# passenger.net
KiCad netlist of a schematic drawn in Altium Designer
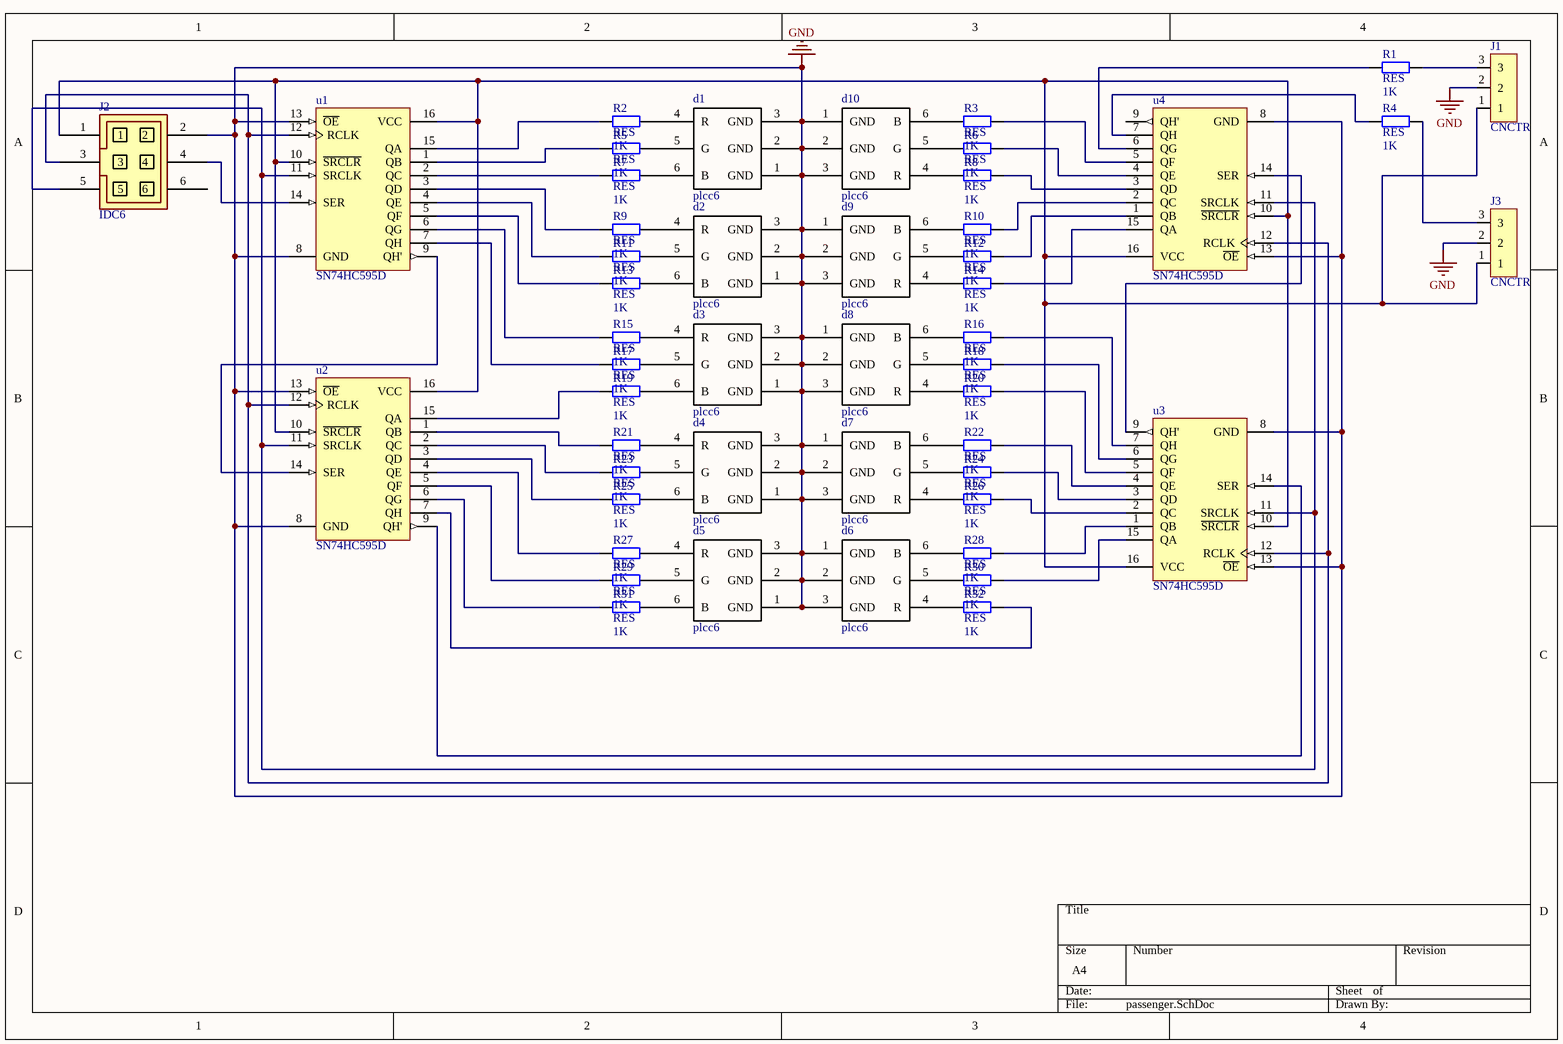
[diagram p0: passenger.SchDoc]

(export (version "E")
  (design (tool "Eeschema 10.0.6"))
  (components
    (comp (ref "d1") (value "plcc6") (footprint "plcc6") (libsource (lib "std") (part "plcc6")))
    (comp (ref "d2") (value "plcc6") (footprint "plcc6") (libsource (lib "std") (part "plcc6")))
    (comp (ref "d3") (value "plcc6") (footprint "plcc6") (libsource (lib "std") (part "plcc6")))
    (comp (ref "d4") (value "plcc6") (footprint "plcc6") (libsource (lib "std") (part "plcc6")))
    (comp (ref "d5") (value "plcc6") (footprint "plcc6") (libsource (lib "std") (part "plcc6")))
    (comp (ref "d6") (value "plcc6") (footprint "plcc6") (libsource (lib "std") (part "plcc6")))
    (comp (ref "d7") (value "plcc6") (footprint "plcc6") (libsource (lib "std") (part "plcc6")))
    (comp (ref "d8") (value "plcc6") (footprint "plcc6") (libsource (lib "std") (part "plcc6")))
    (comp (ref "d9") (value "plcc6") (footprint "plcc6") (libsource (lib "std") (part "plcc6")))
    (comp (ref "d10") (value "plcc6") (footprint "plcc6") (libsource (lib "std") (part "plcc6")))
    (comp (ref "J1")
      (value "CNCTR")
      (footprint "CNCTR_1X3")
      (description "3pin connector")
      (libsource (lib "std") (part "Connector"))
    )
    (comp (ref "J2")
      (value "IDC6")
      (footprint "IDC6")
      (description "6pin IDC connector")
      (libsource (lib "std") (part "IDC6"))
    )
    (comp (ref "J3")
      (value "CNCTR")
      (footprint "CNCTR_1X3")
      (description "3pin connector")
      (libsource (lib "std") (part "Connector"))
    )
    (comp (ref "R1")
      (value "RES")
      (footprint "RESC1608X06M")
      (description "Resistor")
      (fields (field (name "ALTIUM_VALUE") "1K") (field (name "PUBLISHER") "Altium Limited"))
      (libsource (lib "std") (part "RES"))
    )
    (comp (ref "R2")
      (value "RES")
      (footprint "RESC1608X06M")
      (description "Resistor")
      (fields (field (name "ALTIUM_VALUE") "1K") (field (name "PUBLISHER") "Altium Limited"))
      (libsource (lib "std") (part "RES"))
    )
    (comp (ref "R3")
      (value "RES")
      (footprint "RESC1608X06M")
      (description "Resistor")
      (fields (field (name "ALTIUM_VALUE") "1K") (field (name "PUBLISHER") "Altium Limited"))
      (libsource (lib "std") (part "RES"))
    )
    (comp (ref "R4")
      (value "RES")
      (footprint "RESC1608X06M")
      (description "Resistor")
      (fields (field (name "ALTIUM_VALUE") "1K") (field (name "PUBLISHER") "Altium Limited"))
      (libsource (lib "std") (part "RES"))
    )
    (comp (ref "R5")
      (value "RES")
      (footprint "RESC1608X06M")
      (description "Resistor")
      (fields (field (name "ALTIUM_VALUE") "1K") (field (name "PUBLISHER") "Altium Limited"))
      (libsource (lib "std") (part "RES"))
    )
    (comp (ref "R6")
      (value "RES")
      (footprint "RESC1608X06M")
      (description "Resistor")
      (fields (field (name "ALTIUM_VALUE") "1K") (field (name "PUBLISHER") "Altium Limited"))
      (libsource (lib "std") (part "RES"))
    )
    (comp (ref "R7")
      (value "RES")
      (footprint "RESC1608X06M")
      (description "Resistor")
      (fields (field (name "ALTIUM_VALUE") "1K") (field (name "PUBLISHER") "Altium Limited"))
      (libsource (lib "std") (part "RES"))
    )
    (comp (ref "R8")
      (value "RES")
      (footprint "RESC1608X06M")
      (description "Resistor")
      (fields (field (name "ALTIUM_VALUE") "1K") (field (name "PUBLISHER") "Altium Limited"))
      (libsource (lib "std") (part "RES"))
    )
    (comp (ref "R9")
      (value "RES")
      (footprint "RESC1608X06M")
      (description "Resistor")
      (fields (field (name "ALTIUM_VALUE") "1K") (field (name "PUBLISHER") "Altium Limited"))
      (libsource (lib "std") (part "RES"))
    )
    (comp (ref "R10")
      (value "RES")
      (footprint "RESC1608X06M")
      (description "Resistor")
      (fields (field (name "ALTIUM_VALUE") "1K") (field (name "PUBLISHER") "Altium Limited"))
      (libsource (lib "std") (part "RES"))
    )
    (comp (ref "R11")
      (value "RES")
      (footprint "RESC1608X06M")
      (description "Resistor")
      (fields (field (name "ALTIUM_VALUE") "1K") (field (name "PUBLISHER") "Altium Limited"))
      (libsource (lib "std") (part "RES"))
    )
    (comp (ref "R12")
      (value "RES")
      (footprint "RESC1608X06M")
      (description "Resistor")
      (fields (field (name "ALTIUM_VALUE") "1K") (field (name "PUBLISHER") "Altium Limited"))
      (libsource (lib "std") (part "RES"))
    )
    (comp (ref "R13")
      (value "RES")
      (footprint "RESC1608X06M")
      (description "Resistor")
      (fields (field (name "ALTIUM_VALUE") "1K") (field (name "PUBLISHER") "Altium Limited"))
      (libsource (lib "std") (part "RES"))
    )
    (comp (ref "R14")
      (value "RES")
      (footprint "RESC1608X06M")
      (description "Resistor")
      (fields (field (name "ALTIUM_VALUE") "1K") (field (name "PUBLISHER") "Altium Limited"))
      (libsource (lib "std") (part "RES"))
    )
    (comp (ref "R15")
      (value "RES")
      (footprint "RESC1608X06M")
      (description "Resistor")
      (fields (field (name "ALTIUM_VALUE") "1K") (field (name "PUBLISHER") "Altium Limited"))
      (libsource (lib "std") (part "RES"))
    )
    (comp (ref "R16")
      (value "RES")
      (footprint "RESC1608X06M")
      (description "Resistor")
      (fields (field (name "ALTIUM_VALUE") "1K") (field (name "PUBLISHER") "Altium Limited"))
      (libsource (lib "std") (part "RES"))
    )
    (comp (ref "R17")
      (value "RES")
      (footprint "RESC1608X06M")
      (description "Resistor")
      (fields (field (name "ALTIUM_VALUE") "1K") (field (name "PUBLISHER") "Altium Limited"))
      (libsource (lib "std") (part "RES"))
    )
    (comp (ref "R18")
      (value "RES")
      (footprint "RESC1608X06M")
      (description "Resistor")
      (fields (field (name "ALTIUM_VALUE") "1K") (field (name "PUBLISHER") "Altium Limited"))
      (libsource (lib "std") (part "RES"))
    )
    (comp (ref "R19")
      (value "RES")
      (footprint "RESC1608X06M")
      (description "Resistor")
      (fields (field (name "ALTIUM_VALUE") "1K") (field (name "PUBLISHER") "Altium Limited"))
      (libsource (lib "std") (part "RES"))
    )
    (comp (ref "R20")
      (value "RES")
      (footprint "RESC1608X06M")
      (description "Resistor")
      (fields (field (name "ALTIUM_VALUE") "1K") (field (name "PUBLISHER") "Altium Limited"))
      (libsource (lib "std") (part "RES"))
    )
    (comp (ref "R21")
      (value "RES")
      (footprint "RESC1608X06M")
      (description "Resistor")
      (fields (field (name "ALTIUM_VALUE") "1K") (field (name "PUBLISHER") "Altium Limited"))
      (libsource (lib "std") (part "RES"))
    )
    (comp (ref "R22")
      (value "RES")
      (footprint "RESC1608X06M")
      (description "Resistor")
      (fields (field (name "ALTIUM_VALUE") "1K") (field (name "PUBLISHER") "Altium Limited"))
      (libsource (lib "std") (part "RES"))
    )
    (comp (ref "R23")
      (value "RES")
      (footprint "RESC1608X06M")
      (description "Resistor")
      (fields (field (name "ALTIUM_VALUE") "1K") (field (name "PUBLISHER") "Altium Limited"))
      (libsource (lib "std") (part "RES"))
    )
    (comp (ref "R24")
      (value "RES")
      (footprint "RESC1608X06M")
      (description "Resistor")
      (fields (field (name "ALTIUM_VALUE") "1K") (field (name "PUBLISHER") "Altium Limited"))
      (libsource (lib "std") (part "RES"))
    )
    (comp (ref "R25")
      (value "RES")
      (footprint "RESC1608X06M")
      (description "Resistor")
      (fields (field (name "ALTIUM_VALUE") "1K") (field (name "PUBLISHER") "Altium Limited"))
      (libsource (lib "std") (part "RES"))
    )
    (comp (ref "R26")
      (value "RES")
      (footprint "RESC1608X06M")
      (description "Resistor")
      (fields (field (name "ALTIUM_VALUE") "1K") (field (name "PUBLISHER") "Altium Limited"))
      (libsource (lib "std") (part "RES"))
    )
    (comp (ref "R27")
      (value "RES")
      (footprint "RESC1608X06M")
      (description "Resistor")
      (fields (field (name "ALTIUM_VALUE") "1K") (field (name "PUBLISHER") "Altium Limited"))
      (libsource (lib "std") (part "RES"))
    )
    (comp (ref "R28")
      (value "RES")
      (footprint "RESC1608X06M")
      (description "Resistor")
      (fields (field (name "ALTIUM_VALUE") "1K") (field (name "PUBLISHER") "Altium Limited"))
      (libsource (lib "std") (part "RES"))
    )
    (comp (ref "R29")
      (value "RES")
      (footprint "RESC1608X06M")
      (description "Resistor")
      (fields (field (name "ALTIUM_VALUE") "1K") (field (name "PUBLISHER") "Altium Limited"))
      (libsource (lib "std") (part "RES"))
    )
    (comp (ref "R30")
      (value "RES")
      (footprint "RESC1608X06M")
      (description "Resistor")
      (fields (field (name "ALTIUM_VALUE") "1K") (field (name "PUBLISHER") "Altium Limited"))
      (libsource (lib "std") (part "RES"))
    )
    (comp (ref "R31")
      (value "RES")
      (footprint "RESC1608X06M")
      (description "Resistor")
      (fields (field (name "ALTIUM_VALUE") "1K") (field (name "PUBLISHER") "Altium Limited"))
      (libsource (lib "std") (part "RES"))
    )
    (comp (ref "R32")
      (value "RES")
      (footprint "RESC1608X06M")
      (description "Resistor")
      (fields (field (name "ALTIUM_VALUE") "1K") (field (name "PUBLISHER") "Altium Limited"))
      (libsource (lib "std") (part "RES"))
    )
    (comp (ref "u1")
      (value "SN74HC595D")
      (footprint "D016_N")
      (description "8-Bit Shift Register with 3-State Output Registers")
      (fields (field (name "PUBLISHER") "Altium Limited"))
      (libsource (lib "TI Logic Register") (part "SN74HC595D"))
    )
    (comp (ref "u2")
      (value "SN74HC595D")
      (footprint "D016_N")
      (description "8-Bit Shift Register with 3-State Output Registers")
      (fields (field (name "PUBLISHER") "Altium Limited"))
      (libsource (lib "TI Logic Register") (part "SN74HC595D"))
    )
    (comp (ref "u3")
      (value "SN74HC595D")
      (footprint "D016_N")
      (description "8-Bit Shift Register with 3-State Output Registers")
      (fields (field (name "PUBLISHER") "Altium Limited"))
      (libsource (lib "") (part "SN74HC595D_1"))
    )
    (comp (ref "u4")
      (value "SN74HC595D")
      (footprint "D016_N")
      (description "8-Bit Shift Register with 3-State Output Registers")
      (fields (field (name "PUBLISHER") "Altium Limited"))
      (libsource (lib "") (part "SN74HC595D_1"))
    )
  )
  (nets
    (net (code "1") (name "GND") (class "Default")
      (node (ref "J1") (pin "2") (pinfunction "2_2") (pintype "passive"))
      (node (ref "J2") (pin "2") (pinfunction "2_2") (pintype "passive"))
      (node (ref "J3") (pin "2") (pinfunction "2_2") (pintype "passive"))
      (node (ref "d1") (pin "1") (pinfunction "GND_1") (pintype "passive"))
      (node (ref "d1") (pin "2") (pinfunction "GND_2") (pintype "passive"))
      (node (ref "d1") (pin "3") (pinfunction "GND_3") (pintype "passive"))
      (node (ref "d10") (pin "1") (pinfunction "GND_1") (pintype "passive"))
      (node (ref "d10") (pin "2") (pinfunction "GND_2") (pintype "passive"))
      (node (ref "d10") (pin "3") (pinfunction "GND_3") (pintype "passive"))
      (node (ref "d2") (pin "1") (pinfunction "GND_1") (pintype "passive"))
      (node (ref "d2") (pin "2") (pinfunction "GND_2") (pintype "passive"))
      (node (ref "d2") (pin "3") (pinfunction "GND_3") (pintype "passive"))
      (node (ref "d3") (pin "1") (pinfunction "GND_1") (pintype "passive"))
      (node (ref "d3") (pin "2") (pinfunction "GND_2") (pintype "passive"))
      (node (ref "d3") (pin "3") (pinfunction "GND_3") (pintype "passive"))
      (node (ref "d4") (pin "1") (pinfunction "GND_1") (pintype "passive"))
      (node (ref "d4") (pin "2") (pinfunction "GND_2") (pintype "passive"))
      (node (ref "d4") (pin "3") (pinfunction "GND_3") (pintype "passive"))
      (node (ref "d5") (pin "1") (pinfunction "GND_1") (pintype "passive"))
      (node (ref "d5") (pin "2") (pinfunction "GND_2") (pintype "passive"))
      (node (ref "d5") (pin "3") (pinfunction "GND_3") (pintype "passive"))
      (node (ref "d6") (pin "1") (pinfunction "GND_1") (pintype "passive"))
      (node (ref "d6") (pin "2") (pinfunction "GND_2") (pintype "passive"))
      (node (ref "d6") (pin "3") (pinfunction "GND_3") (pintype "passive"))
      (node (ref "d7") (pin "1") (pinfunction "GND_1") (pintype "passive"))
      (node (ref "d7") (pin "2") (pinfunction "GND_2") (pintype "passive"))
      (node (ref "d7") (pin "3") (pinfunction "GND_3") (pintype "passive"))
      (node (ref "d8") (pin "1") (pinfunction "GND_1") (pintype "passive"))
      (node (ref "d8") (pin "2") (pinfunction "GND_2") (pintype "passive"))
      (node (ref "d8") (pin "3") (pinfunction "GND_3") (pintype "passive"))
      (node (ref "d9") (pin "1") (pinfunction "GND_1") (pintype "passive"))
      (node (ref "d9") (pin "2") (pinfunction "GND_2") (pintype "passive"))
      (node (ref "d9") (pin "3") (pinfunction "GND_3") (pintype "passive"))
      (node (ref "u1") (pin "13") (pinfunction "~{OE}_13") (pintype "input"))
      (node (ref "u1") (pin "8") (pinfunction "GND_8") (pintype "power_in"))
      (node (ref "u2") (pin "13") (pinfunction "~{OE}_13") (pintype "input"))
      (node (ref "u2") (pin "8") (pinfunction "GND_8") (pintype "power_in"))
      (node (ref "u3") (pin "13") (pinfunction "~{OE}_13") (pintype "input"))
      (node (ref "u3") (pin "8") (pinfunction "GND_8") (pintype "power_in"))
      (node (ref "u4") (pin "13") (pinfunction "~{OE}_13") (pintype "input"))
      (node (ref "u4") (pin "8") (pinfunction "GND_8") (pintype "power_in"))
    )
    (net (code "2") (name "Net-(J1-Pad3)") (class "Default")
      (node (ref "J1") (pin "3") (pinfunction "3_3") (pintype "passive"))
      (node (ref "R1") (pin "2") (pinfunction "2_2") (pintype "passive"))
    )
    (net (code "3") (name "Net-(J3-Pad3)") (class "Default")
      (node (ref "J3") (pin "3") (pinfunction "3_3") (pintype "passive"))
      (node (ref "R4") (pin "2") (pinfunction "2_2") (pintype "passive"))
    )
    (net (code "4") (name "Net-(d1-B)") (class "Default")
      (node (ref "R7") (pin "2") (pinfunction "2_2") (pintype "passive"))
      (node (ref "d1") (pin "6") (pinfunction "B_6") (pintype "passive"))
    )
    (net (code "5") (name "Net-(d1-G)") (class "Default")
      (node (ref "R5") (pin "2") (pinfunction "2_2") (pintype "passive"))
      (node (ref "d1") (pin "5") (pinfunction "G_5") (pintype "passive"))
    )
    (net (code "6") (name "Net-(d1-R)") (class "Default")
      (node (ref "R2") (pin "2") (pinfunction "2_2") (pintype "passive"))
      (node (ref "d1") (pin "4") (pinfunction "R_4") (pintype "passive"))
    )
    (net (code "7") (name "Net-(d2-B)") (class "Default")
      (node (ref "R13") (pin "2") (pinfunction "2_2") (pintype "passive"))
      (node (ref "d2") (pin "6") (pinfunction "B_6") (pintype "passive"))
    )
    (net (code "8") (name "Net-(d2-G)") (class "Default")
      (node (ref "R11") (pin "2") (pinfunction "2_2") (pintype "passive"))
      (node (ref "d2") (pin "5") (pinfunction "G_5") (pintype "passive"))
    )
    (net (code "9") (name "Net-(d2-R)") (class "Default")
      (node (ref "R9") (pin "2") (pinfunction "2_2") (pintype "passive"))
      (node (ref "d2") (pin "4") (pinfunction "R_4") (pintype "passive"))
    )
    (net (code "10") (name "Net-(d3-B)") (class "Default")
      (node (ref "R19") (pin "2") (pinfunction "2_2") (pintype "passive"))
      (node (ref "d3") (pin "6") (pinfunction "B_6") (pintype "passive"))
    )
    (net (code "11") (name "Net-(d3-G)") (class "Default")
      (node (ref "R17") (pin "2") (pinfunction "2_2") (pintype "passive"))
      (node (ref "d3") (pin "5") (pinfunction "G_5") (pintype "passive"))
    )
    (net (code "12") (name "Net-(d3-R)") (class "Default")
      (node (ref "R15") (pin "2") (pinfunction "2_2") (pintype "passive"))
      (node (ref "d3") (pin "4") (pinfunction "R_4") (pintype "passive"))
    )
    (net (code "13") (name "Net-(d4-B)") (class "Default")
      (node (ref "R25") (pin "2") (pinfunction "2_2") (pintype "passive"))
      (node (ref "d4") (pin "6") (pinfunction "B_6") (pintype "passive"))
    )
    (net (code "14") (name "Net-(d4-G)") (class "Default")
      (node (ref "R23") (pin "2") (pinfunction "2_2") (pintype "passive"))
      (node (ref "d4") (pin "5") (pinfunction "G_5") (pintype "passive"))
    )
    (net (code "15") (name "Net-(d4-R)") (class "Default")
      (node (ref "R21") (pin "2") (pinfunction "2_2") (pintype "passive"))
      (node (ref "d4") (pin "4") (pinfunction "R_4") (pintype "passive"))
    )
    (net (code "16") (name "Net-(d5-B)") (class "Default")
      (node (ref "R31") (pin "2") (pinfunction "2_2") (pintype "passive"))
      (node (ref "d5") (pin "6") (pinfunction "B_6") (pintype "passive"))
    )
    (net (code "17") (name "Net-(d5-G)") (class "Default")
      (node (ref "R29") (pin "2") (pinfunction "2_2") (pintype "passive"))
      (node (ref "d5") (pin "5") (pinfunction "G_5") (pintype "passive"))
    )
    (net (code "18") (name "Net-(d5-R)") (class "Default")
      (node (ref "R27") (pin "2") (pinfunction "2_2") (pintype "passive"))
      (node (ref "d5") (pin "4") (pinfunction "R_4") (pintype "passive"))
    )
    (net (code "19") (name "Net-(d6-B)") (class "Default")
      (node (ref "R28") (pin "1") (pinfunction "1_1") (pintype "passive"))
      (node (ref "d6") (pin "6") (pinfunction "B_6") (pintype "passive"))
    )
    (net (code "20") (name "Net-(d6-G)") (class "Default")
      (node (ref "R30") (pin "1") (pinfunction "1_1") (pintype "passive"))
      (node (ref "d6") (pin "5") (pinfunction "G_5") (pintype "passive"))
    )
    (net (code "21") (name "Net-(d6-R)") (class "Default")
      (node (ref "R32") (pin "1") (pinfunction "1_1") (pintype "passive"))
      (node (ref "d6") (pin "4") (pinfunction "R_4") (pintype "passive"))
    )
    (net (code "22") (name "Net-(d7-B)") (class "Default")
      (node (ref "R22") (pin "1") (pinfunction "1_1") (pintype "passive"))
      (node (ref "d7") (pin "6") (pinfunction "B_6") (pintype "passive"))
    )
    (net (code "23") (name "Net-(d7-G)") (class "Default")
      (node (ref "R24") (pin "1") (pinfunction "1_1") (pintype "passive"))
      (node (ref "d7") (pin "5") (pinfunction "G_5") (pintype "passive"))
    )
    (net (code "24") (name "Net-(d7-R)") (class "Default")
      (node (ref "R26") (pin "1") (pinfunction "1_1") (pintype "passive"))
      (node (ref "d7") (pin "4") (pinfunction "R_4") (pintype "passive"))
    )
    (net (code "25") (name "Net-(d8-B)") (class "Default")
      (node (ref "R16") (pin "1") (pinfunction "1_1") (pintype "passive"))
      (node (ref "d8") (pin "6") (pinfunction "B_6") (pintype "passive"))
    )
    (net (code "26") (name "Net-(d8-G)") (class "Default")
      (node (ref "R18") (pin "1") (pinfunction "1_1") (pintype "passive"))
      (node (ref "d8") (pin "5") (pinfunction "G_5") (pintype "passive"))
    )
    (net (code "27") (name "Net-(d8-R)") (class "Default")
      (node (ref "R20") (pin "1") (pinfunction "1_1") (pintype "passive"))
      (node (ref "d8") (pin "4") (pinfunction "R_4") (pintype "passive"))
    )
    (net (code "28") (name "Net-(d9-B)") (class "Default")
      (node (ref "R10") (pin "1") (pinfunction "1_1") (pintype "passive"))
      (node (ref "d9") (pin "6") (pinfunction "B_6") (pintype "passive"))
    )
    (net (code "29") (name "Net-(d9-G)") (class "Default")
      (node (ref "R12") (pin "1") (pinfunction "1_1") (pintype "passive"))
      (node (ref "d9") (pin "5") (pinfunction "G_5") (pintype "passive"))
    )
    (net (code "30") (name "Net-(d9-R)") (class "Default")
      (node (ref "R14") (pin "1") (pinfunction "1_1") (pintype "passive"))
      (node (ref "d9") (pin "4") (pinfunction "R_4") (pintype "passive"))
    )
    (net (code "31") (name "Net-(d10-B)") (class "Default")
      (node (ref "R3") (pin "1") (pinfunction "1_1") (pintype "passive"))
      (node (ref "d10") (pin "6") (pinfunction "B_6") (pintype "passive"))
    )
    (net (code "32") (name "Net-(d10-G)") (class "Default")
      (node (ref "R6") (pin "1") (pinfunction "1_1") (pintype "passive"))
      (node (ref "d10") (pin "5") (pinfunction "G_5") (pintype "passive"))
    )
    (net (code "33") (name "Net-(d10-R)") (class "Default")
      (node (ref "R8") (pin "1") (pinfunction "1_1") (pintype "passive"))
      (node (ref "d10") (pin "4") (pinfunction "R_4") (pintype "passive"))
    )
    (net (code "34") (name "Net-(u1-QA)") (class "Default")
      (node (ref "R2") (pin "1") (pinfunction "1_1") (pintype "passive"))
      (node (ref "u1") (pin "15") (pinfunction "QA_15") (pintype "tri_state"))
    )
    (net (code "35") (name "Net-(u1-QB)") (class "Default")
      (node (ref "R5") (pin "1") (pinfunction "1_1") (pintype "passive"))
      (node (ref "u1") (pin "1") (pinfunction "QB_1") (pintype "tri_state"))
    )
    (net (code "36") (name "Net-(u1-QC)") (class "Default")
      (node (ref "R7") (pin "1") (pinfunction "1_1") (pintype "passive"))
      (node (ref "u1") (pin "2") (pinfunction "QC_2") (pintype "tri_state"))
    )
    (net (code "37") (name "Net-(u1-QD)") (class "Default")
      (node (ref "R9") (pin "1") (pinfunction "1_1") (pintype "passive"))
      (node (ref "u1") (pin "3") (pinfunction "QD_3") (pintype "tri_state"))
    )
    (net (code "38") (name "Net-(u1-QE)") (class "Default")
      (node (ref "R11") (pin "1") (pinfunction "1_1") (pintype "passive"))
      (node (ref "u1") (pin "4") (pinfunction "QE_4") (pintype "tri_state"))
    )
    (net (code "39") (name "Net-(u1-QF)") (class "Default")
      (node (ref "R13") (pin "1") (pinfunction "1_1") (pintype "passive"))
      (node (ref "u1") (pin "5") (pinfunction "QF_5") (pintype "tri_state"))
    )
    (net (code "40") (name "Net-(u1-QG)") (class "Default")
      (node (ref "R15") (pin "1") (pinfunction "1_1") (pintype "passive"))
      (node (ref "u1") (pin "6") (pinfunction "QG_6") (pintype "tri_state"))
    )
    (net (code "41") (name "Net-(u1-QH')") (class "Default")
      (node (ref "u1") (pin "9") (pinfunction "QH'_9") (pintype "output"))
      (node (ref "u2") (pin "14") (pinfunction "SER_14") (pintype "input"))
    )
    (net (code "42") (name "Net-(u1-QH)") (class "Default")
      (node (ref "R17") (pin "1") (pinfunction "1_1") (pintype "passive"))
      (node (ref "u1") (pin "7") (pinfunction "QH_7") (pintype "tri_state"))
    )
    (net (code "43") (name "Net-(u1-RCLK)") (class "Default")
      (node (ref "J2") (pin "3") (pinfunction "3_3") (pintype "passive"))
      (node (ref "u1") (pin "12") (pinfunction "RCLK_12") (pintype "input"))
      (node (ref "u2") (pin "12") (pinfunction "RCLK_12") (pintype "input"))
      (node (ref "u3") (pin "12") (pinfunction "RCLK_12") (pintype "input"))
      (node (ref "u4") (pin "12") (pinfunction "RCLK_12") (pintype "input"))
    )
    (net (code "44") (name "Net-(u1-SER)") (class "Default")
      (node (ref "J2") (pin "4") (pinfunction "4_4") (pintype "passive"))
      (node (ref "u1") (pin "14") (pinfunction "SER_14") (pintype "input"))
    )
    (net (code "45") (name "Net-(u1-SRCLK)") (class "Default")
      (node (ref "J2") (pin "5") (pinfunction "5_5") (pintype "passive"))
      (node (ref "u1") (pin "11") (pinfunction "SRCLK_11") (pintype "input"))
      (node (ref "u2") (pin "11") (pinfunction "SRCLK_11") (pintype "input"))
      (node (ref "u3") (pin "11") (pinfunction "SRCLK_11") (pintype "input"))
      (node (ref "u4") (pin "11") (pinfunction "SRCLK_11") (pintype "input"))
    )
    (net (code "46") (name "Net-(u1-VCC)") (class "Default")
      (node (ref "J1") (pin "1") (pinfunction "1_1") (pintype "passive"))
      (node (ref "J2") (pin "1") (pinfunction "1_1") (pintype "passive"))
      (node (ref "J3") (pin "1") (pinfunction "1_1") (pintype "passive"))
      (node (ref "u1") (pin "10") (pinfunction "~{SRCLR}_10") (pintype "input"))
      (node (ref "u1") (pin "16") (pinfunction "VCC_16") (pintype "power_in"))
      (node (ref "u2") (pin "10") (pinfunction "~{SRCLR}_10") (pintype "input"))
      (node (ref "u2") (pin "16") (pinfunction "VCC_16") (pintype "power_in"))
      (node (ref "u3") (pin "10") (pinfunction "~{SRCLR}_10") (pintype "input"))
      (node (ref "u3") (pin "16") (pinfunction "VCC_16") (pintype "power_in"))
      (node (ref "u4") (pin "10") (pinfunction "~{SRCLR}_10") (pintype "input"))
      (node (ref "u4") (pin "16") (pinfunction "VCC_16") (pintype "power_in"))
    )
    (net (code "47") (name "Net-(u2-QA)") (class "Default")
      (node (ref "R19") (pin "1") (pinfunction "1_1") (pintype "passive"))
      (node (ref "u2") (pin "15") (pinfunction "QA_15") (pintype "tri_state"))
    )
    (net (code "48") (name "Net-(u2-QB)") (class "Default")
      (node (ref "R21") (pin "1") (pinfunction "1_1") (pintype "passive"))
      (node (ref "u2") (pin "1") (pinfunction "QB_1") (pintype "tri_state"))
    )
    (net (code "49") (name "Net-(u2-QC)") (class "Default")
      (node (ref "R23") (pin "1") (pinfunction "1_1") (pintype "passive"))
      (node (ref "u2") (pin "2") (pinfunction "QC_2") (pintype "tri_state"))
    )
    (net (code "50") (name "Net-(u2-QD)") (class "Default")
      (node (ref "R25") (pin "1") (pinfunction "1_1") (pintype "passive"))
      (node (ref "u2") (pin "3") (pinfunction "QD_3") (pintype "tri_state"))
    )
    (net (code "51") (name "Net-(u2-QE)") (class "Default")
      (node (ref "R27") (pin "1") (pinfunction "1_1") (pintype "passive"))
      (node (ref "u2") (pin "4") (pinfunction "QE_4") (pintype "tri_state"))
    )
    (net (code "52") (name "Net-(u2-QF)") (class "Default")
      (node (ref "R29") (pin "1") (pinfunction "1_1") (pintype "passive"))
      (node (ref "u2") (pin "5") (pinfunction "QF_5") (pintype "tri_state"))
    )
    (net (code "53") (name "Net-(u2-QG)") (class "Default")
      (node (ref "R31") (pin "1") (pinfunction "1_1") (pintype "passive"))
      (node (ref "u2") (pin "6") (pinfunction "QG_6") (pintype "tri_state"))
    )
    (net (code "54") (name "Net-(u2-QH')") (class "Default")
      (node (ref "u2") (pin "9") (pinfunction "QH'_9") (pintype "output"))
      (node (ref "u3") (pin "14") (pinfunction "SER_14") (pintype "input"))
    )
    (net (code "55") (name "Net-(u2-QH)") (class "Default")
      (node (ref "R32") (pin "2") (pinfunction "2_2") (pintype "passive"))
      (node (ref "u2") (pin "7") (pinfunction "QH_7") (pintype "tri_state"))
    )
    (net (code "56") (name "Net-(u3-QA)") (class "Default")
      (node (ref "R30") (pin "2") (pinfunction "2_2") (pintype "passive"))
      (node (ref "u3") (pin "15") (pinfunction "QA_15") (pintype "tri_state"))
    )
    (net (code "57") (name "Net-(u3-QB)") (class "Default")
      (node (ref "R28") (pin "2") (pinfunction "2_2") (pintype "passive"))
      (node (ref "u3") (pin "1") (pinfunction "QB_1") (pintype "tri_state"))
    )
    (net (code "58") (name "Net-(u3-QC)") (class "Default")
      (node (ref "R26") (pin "2") (pinfunction "2_2") (pintype "passive"))
      (node (ref "u3") (pin "2") (pinfunction "QC_2") (pintype "tri_state"))
    )
    (net (code "59") (name "Net-(u3-QD)") (class "Default")
      (node (ref "R24") (pin "2") (pinfunction "2_2") (pintype "passive"))
      (node (ref "u3") (pin "3") (pinfunction "QD_3") (pintype "tri_state"))
    )
    (net (code "60") (name "Net-(u3-QE)") (class "Default")
      (node (ref "R22") (pin "2") (pinfunction "2_2") (pintype "passive"))
      (node (ref "u3") (pin "4") (pinfunction "QE_4") (pintype "tri_state"))
    )
    (net (code "61") (name "Net-(u3-QF)") (class "Default")
      (node (ref "R20") (pin "2") (pinfunction "2_2") (pintype "passive"))
      (node (ref "u3") (pin "5") (pinfunction "QF_5") (pintype "tri_state"))
    )
    (net (code "62") (name "Net-(u3-QG)") (class "Default")
      (node (ref "R18") (pin "2") (pinfunction "2_2") (pintype "passive"))
      (node (ref "u3") (pin "6") (pinfunction "QG_6") (pintype "tri_state"))
    )
    (net (code "63") (name "Net-(u3-QH')") (class "Default")
      (node (ref "u3") (pin "9") (pinfunction "QH'_9") (pintype "output"))
      (node (ref "u4") (pin "14") (pinfunction "SER_14") (pintype "input"))
    )
    (net (code "64") (name "Net-(u3-QH)") (class "Default")
      (node (ref "R16") (pin "2") (pinfunction "2_2") (pintype "passive"))
      (node (ref "u3") (pin "7") (pinfunction "QH_7") (pintype "tri_state"))
    )
    (net (code "65") (name "Net-(u4-QA)") (class "Default")
      (node (ref "R14") (pin "2") (pinfunction "2_2") (pintype "passive"))
      (node (ref "u4") (pin "15") (pinfunction "QA_15") (pintype "tri_state"))
    )
    (net (code "66") (name "Net-(u4-QB)") (class "Default")
      (node (ref "R12") (pin "2") (pinfunction "2_2") (pintype "passive"))
      (node (ref "u4") (pin "1") (pinfunction "QB_1") (pintype "tri_state"))
    )
    (net (code "67") (name "Net-(u4-QC)") (class "Default")
      (node (ref "R10") (pin "2") (pinfunction "2_2") (pintype "passive"))
      (node (ref "u4") (pin "2") (pinfunction "QC_2") (pintype "tri_state"))
    )
    (net (code "68") (name "Net-(u4-QD)") (class "Default")
      (node (ref "R8") (pin "2") (pinfunction "2_2") (pintype "passive"))
      (node (ref "u4") (pin "3") (pinfunction "QD_3") (pintype "tri_state"))
    )
    (net (code "69") (name "Net-(u4-QE)") (class "Default")
      (node (ref "R6") (pin "2") (pinfunction "2_2") (pintype "passive"))
      (node (ref "u4") (pin "4") (pinfunction "QE_4") (pintype "tri_state"))
    )
    (net (code "70") (name "Net-(u4-QF)") (class "Default")
      (node (ref "R3") (pin "2") (pinfunction "2_2") (pintype "passive"))
      (node (ref "u4") (pin "5") (pinfunction "QF_5") (pintype "tri_state"))
    )
    (net (code "71") (name "Net-(u4-QG)") (class "Default")
      (node (ref "R1") (pin "1") (pinfunction "1_1") (pintype "passive"))
      (node (ref "u4") (pin "6") (pinfunction "QG_6") (pintype "tri_state"))
    )
    (net (code "72") (name "Net-(u4-QH)") (class "Default")
      (node (ref "R4") (pin "1") (pinfunction "1_1") (pintype "passive"))
      (node (ref "u4") (pin "7") (pinfunction "QH_7") (pintype "tri_state"))
    )
    (net (code "73") (name "unconnected-(J2-Pad6)") (class "Default")
      (node (ref "J2") (pin "6") (pinfunction "6_6") (pintype "passive"))
    )
    (net (code "74") (name "unconnected-(u4-QH'-Pad9)") (class "Default")
      (node (ref "u4") (pin "9") (pinfunction "QH'_9") (pintype "output"))
    )
  )
)
